# BypassUnit.net
KiCad netlist of a schematic drawn in Altium Designer
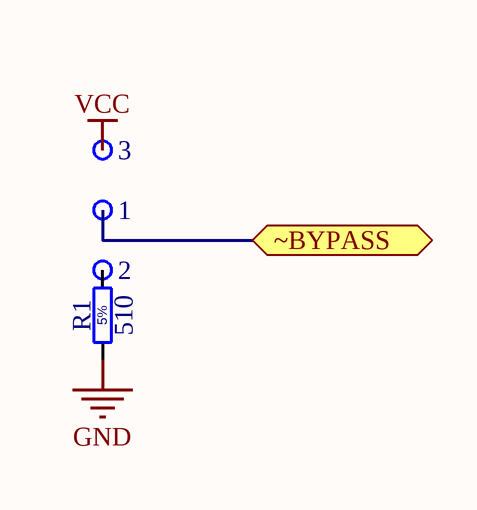
[diagram p0: BypassUnit.SchDoc]

(export (version "E")
  (design (tool "Eeschema 10.0.6"))
  (components
    (comp (ref "1")
      (value "Plated Hole")
      (footprint "c180h130")
      (description "Single Terminal Socket")
      (fields (field (name "PART NUMBER") "PLATED_HOLE1.3_PAD1.8") (field (name "AUTHOR") "CERN DEM JLC"))
      (libsource (lib "Eletro-mechanical") (part "Single Terminal Socket"))
    )
    (comp (ref "2")
      (value "Plated Hole")
      (footprint "c180h130")
      (description "Single Terminal Socket")
      (fields (field (name "PART NUMBER") "PLATED_HOLE1.3_PAD1.8") (field (name "AUTHOR") "CERN DEM JLC"))
      (libsource (lib "Eletro-mechanical") (part "Single Terminal Socket"))
    )
    (comp (ref "3")
      (value "Plated Hole")
      (footprint "c180h130")
      (description "Single Terminal Socket")
      (fields (field (name "PART NUMBER") "PLATED_HOLE1.3_PAD1.8") (field (name "AUTHOR") "CERN DEM JLC"))
      (libsource (lib "Eletro-mechanical") (part "Single Terminal Socket"))
    )
    (comp (ref "R1")
      (value "510")
      (footprint "RES_ARCOL_RCC025")
      (description "Resistor - 5%")
      (fields
        (field (name "PART NUMBER") "RCF_5K1_5%_0.25W_+10-6PPM_ARCOL_RCC025")
        (field (name "POWER") "0.25W")
        (field (name "AUTHOR") "CERN DEM JLC")
      )
      (libsource (lib "Resistors") (part "Resistor - 5%"))
    )
  )
  (nets
    (net (code "1") (name "/~BYPASS") (class "Default")
      (node (ref "1") (pin "1") (pinfunction "1_1") (pintype "bidirectional"))
    )
    (net (code "2") (name "GND") (class "Default")
      (node (ref "R1") (pin "1") (pinfunction "1_1") (pintype "passive"))
    )
    (net (code "3") (name "Net-(2-Pad1)") (class "Default")
      (node (ref "2") (pin "1") (pinfunction "1_1") (pintype "bidirectional"))
      (node (ref "R1") (pin "2") (pinfunction "2_2") (pintype "passive"))
    )
    (net (code "4") (name "VCC") (class "Default")
      (node (ref "3") (pin "1") (pinfunction "1_1") (pintype "bidirectional"))
    )
  )
)
